# ws2812_2020_breakout.net
KiCad netlist of a schematic drawn in Altium Designer
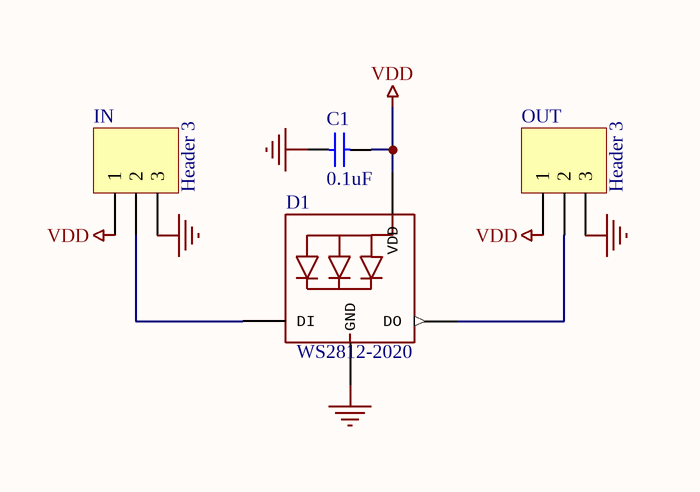
[diagram p0: ws2812_2020_breakout.SchDoc]

(export (version "E")
  (design (tool "Eeschema 10.0.6"))
  (components
    (comp (ref "C1")
      (value "0.1uF")
      (footprint "CAP_0402R")
      (description "Capacitor")
      (libsource (lib "ws2812_2020_breakout") (part "CAP"))
    )
    (comp (ref "D1")
      (value "WS2812-2020")
      (footprint "WS2812-2020")
      (description "Intelligent control LED integrated light source, low current, 2020 package")
      (fields (field (name "MANUFACTURER") "Worldsemi"))
      (libsource (lib "ws2812_2020_breakout") (part "WS2812-2020"))
    )
    (comp (ref "IN")
      (value "Header 3")
      (footprint "HDR1X3")
      (description "Header, 3-Pin")
      (libsource (lib "ws2812_2020_breakout") (part "Header 3"))
    )
    (comp (ref "OUT")
      (value "Header 3")
      (footprint "HDR1X3")
      (description "Header, 3-Pin")
      (libsource (lib "ws2812_2020_breakout") (part "Header 3"))
    )
  )
  (nets
    (net (code "1") (name "GND") (class "Default")
      (node (ref "C1") (pin "1") (pinfunction "1_1") (pintype "passive"))
      (node (ref "D1") (pin "2") (pinfunction "GND_2") (pintype "power_in"))
      (node (ref "IN") (pin "3") (pinfunction "3_3") (pintype "passive"))
      (node (ref "OUT") (pin "3") (pinfunction "3_3") (pintype "passive"))
    )
    (net (code "2") (name "Net-(D1-DI)") (class "Default")
      (node (ref "D1") (pin "3") (pinfunction "DI_3") (pintype "passive"))
      (node (ref "IN") (pin "2") (pinfunction "2_2") (pintype "passive"))
    )
    (net (code "3") (name "Net-(D1-DO)") (class "Default")
      (node (ref "D1") (pin "1") (pinfunction "DO_1") (pintype "output"))
      (node (ref "OUT") (pin "2") (pinfunction "2_2") (pintype "passive"))
    )
    (net (code "4") (name "VDD") (class "Default")
      (node (ref "C1") (pin "2") (pinfunction "2_2") (pintype "passive"))
      (node (ref "D1") (pin "4") (pinfunction "VDD_4") (pintype "power_in"))
      (node (ref "IN") (pin "1") (pinfunction "1_1") (pintype "passive"))
      (node (ref "OUT") (pin "1") (pinfunction "1_1") (pintype "passive"))
    )
  )
)
